# Power_Supply_Test.net
KiCad netlist of a schematic drawn in Altium Designer
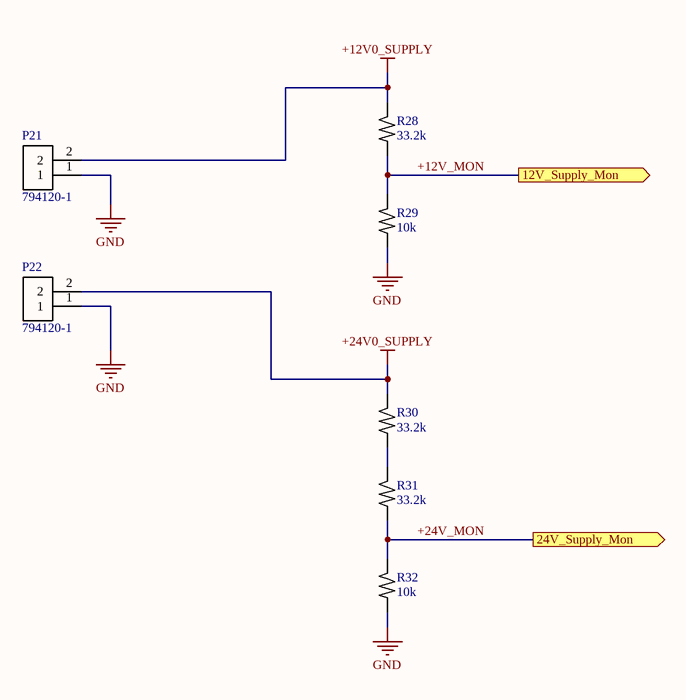
[diagram p0: Power Supply Test.SchDoc]

(export (version "E")
  (design (tool "Eeschema 10.0.6"))
  (components
    (comp (ref "P21")
      (value "794120-1")
      (footprint "POWER2-5.08 right angle")
      (fields (field (name "MP") "TE Connectivity"))
      (libsource (lib "Connectors") (part "Power2"))
    )
    (comp (ref "P22")
      (value "794120-1")
      (footprint "POWER2-5.08 right angle")
      (fields (field (name "MP") "TE Connectivity"))
      (libsource (lib "Connectors") (part "Power2"))
    )
    (comp (ref "R28")
      (value "33.2k")
      (footprint "R0603")
      (description "RES 33.2kΩ ±1% 100mW 0603")
      (fields (field (name "MF") "FOJAN") (field (name "MP") "FRC0603F3322TS"))
      (libsource (lib "Components") (part "Res"))
    )
    (comp (ref "R29")
      (value "10k")
      (footprint "R0603")
      (description "RES 10kΩ ±1% 100mW 0603")
      (fields (field (name "MF") "FOJAN") (field (name "MP") "FRC0603F1002TS"))
      (libsource (lib "Components") (part "Res"))
    )
    (comp (ref "R30")
      (value "33.2k")
      (footprint "R0603")
      (description "RES 33.2kΩ ±1% 100mW 0603")
      (fields (field (name "MF") "FOJAN") (field (name "MP") "FRC0603F3322TS"))
      (libsource (lib "Components") (part "Res"))
    )
    (comp (ref "R31")
      (value "33.2k")
      (footprint "R0603")
      (description "RES 33.2kΩ ±1% 100mW 0603")
      (fields (field (name "MF") "FOJAN") (field (name "MP") "FRC0603F3322TS"))
      (libsource (lib "Components") (part "Res"))
    )
    (comp (ref "R32")
      (value "10k")
      (footprint "R0603")
      (description "RES 10kΩ ±1% 100mW 0603")
      (fields (field (name "MF") "FOJAN") (field (name "MP") "FRC0603F1002TS"))
      (libsource (lib "Components") (part "Res"))
    )
  )
  (nets
    (net (code "1") (name "+12V0_SUPPLY") (class "Default")
      (node (ref "P21") (pin "2") (pinfunction "2_2") (pintype "passive"))
      (node (ref "R28") (pin "2") (pinfunction "2_2") (pintype "passive"))
    )
    (net (code "2") (name "+24V0_SUPPLY") (class "Default")
      (node (ref "P22") (pin "2") (pinfunction "2_2") (pintype "passive"))
      (node (ref "R30") (pin "2") (pinfunction "2_2") (pintype "passive"))
    )
    (net (code "3") (name "/+12V_MON") (class "Default")
      (node (ref "R28") (pin "1") (pinfunction "1_1") (pintype "passive"))
      (node (ref "R29") (pin "2") (pinfunction "2_2") (pintype "passive"))
    )
    (net (code "4") (name "/+24V_MON") (class "Default")
      (node (ref "R31") (pin "1") (pinfunction "1_1") (pintype "passive"))
      (node (ref "R32") (pin "2") (pinfunction "2_2") (pintype "passive"))
    )
    (net (code "5") (name "GND") (class "Default")
      (node (ref "P21") (pin "1") (pinfunction "1_1") (pintype "passive"))
      (node (ref "P22") (pin "1") (pinfunction "1_1") (pintype "passive"))
      (node (ref "R29") (pin "1") (pinfunction "1_1") (pintype "passive"))
      (node (ref "R32") (pin "1") (pinfunction "1_1") (pintype "passive"))
    )
    (net (code "6") (name "Net-(R30-Pad1)") (class "Default")
      (node (ref "R30") (pin "1") (pinfunction "1_1") (pintype "passive"))
      (node (ref "R31") (pin "2") (pinfunction "2_2") (pintype "passive"))
    )
  )
)
